# PX4FLOW2_0_CPU_X0.net
KiCad netlist of a schematic drawn in Altium Designer
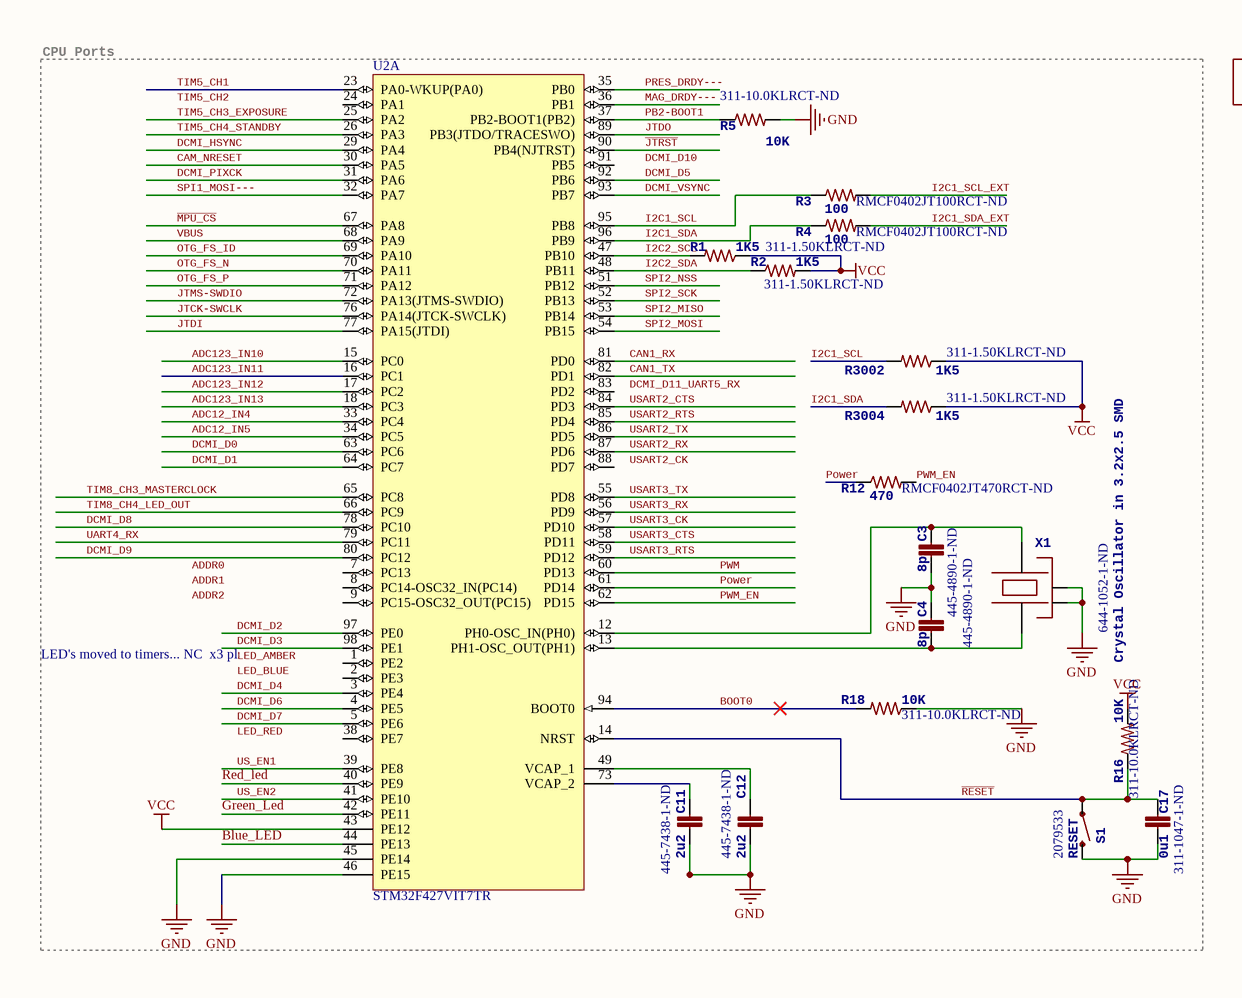
[diagram p0: PX4FLOW2.0_CPU_X0.SchDoc, left]
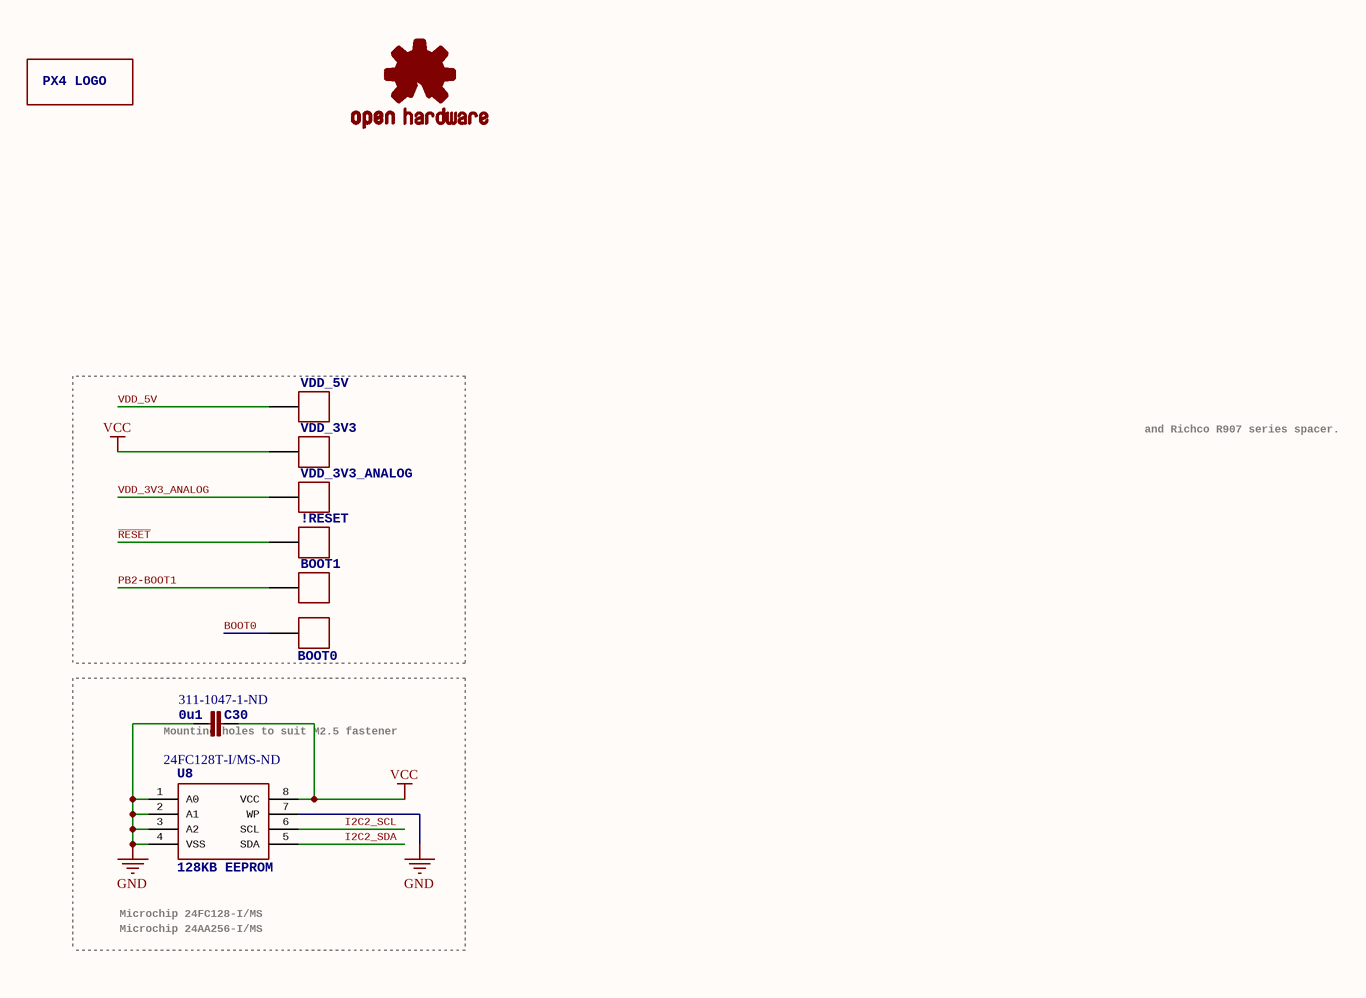
[diagram p1: PX4FLOW2.0_CPU_X0.SchDoc, right]

(export (version "E")
  (design (tool "Eeschema 10.0.6"))
  (components
    (comp (ref "!RESET") (value "PAD.04") (footprint "PAD.04X.04") (libsource (lib "") (part "PAD.04_1")))
    (comp (ref "BOOT0")
      (value "PAD.05")
      (footprint "PAD.05X.05")
      (libsource (lib "pixhawk2") (part "PAD.05"))
    )
    (comp (ref "BOOT1")
      (value "PAD.04")
      (footprint "PAD.04X.04")
      (libsource (lib "pixhawk2") (part "PAD.04"))
    )
    (comp (ref "C3")
      (value "8p")
      (footprint "0402-CAP")
      (description "CAP CER 8PF 50V C0G 0402")
      (fields
        (field (name "PARTNO") "C1005C0G1H080C")
        (field (name "SUPPLIER PART NUMBER 1") "445-4890-1-ND")
        (field (name "3DR_PARTNO") "ECM0710")
      )
      (libsource (lib "pixhawk2") (part "CAP0402"))
    )
    (comp (ref "C4")
      (value "8p")
      (footprint "0402-CAP")
      (description "CAP CER 8PF 50V C0G 0402")
      (fields
        (field (name "PARTNO") "C1005C0G1H080C")
        (field (name "SUPPLIER PART NUMBER 1") "445-4890-1-ND")
        (field (name "3DR_PARTNO") "ECM0710")
      )
      (libsource (lib "pixhawk2") (part "CAP0402"))
    )
    (comp (ref "C11")
      (value "2u2")
      (footprint "0603-CAP")
      (description "Capacitor, 2.2uF, 16V, 10%, X6S, 0603, Ceramic")
      (fields
        (field (name "PARTNO") "C1608X6S1C225K080AC")
        (field (name "SUPPLIER PART NUMBER 1") "445-7438-1-ND")
        (field (name "3DR_PARTNO") "ECM0619")
      )
      (libsource (lib "pixhawk2") (part "CAP0603"))
    )
    (comp (ref "C12")
      (value "2u2")
      (footprint "0603-CAP")
      (description "Capacitor, 2.2uF, 16V, 10%, X6S, 0603, Ceramic")
      (fields
        (field (name "PARTNO") "C1608X6S1C225K080AC")
        (field (name "SUPPLIER PART NUMBER 1") "445-7438-1-ND")
        (field (name "3DR_PARTNO") "ECM0619")
      )
      (libsource (lib "pixhawk2") (part "CAP0603"))
    )
    (comp (ref "C17")
      (value "0u1")
      (footprint "0402-CAP")
      (description "CapacitorStandard 0603 ceramic capacitor, and 0.1\" leaded capacitor.")
      (fields
        (field (name "PARTNO") "CC0402ZRY5V7BB104")
        (field (name "SUPPLIER PART NUMBER 1") "311-1047-1-ND")
      )
      (libsource (lib "pixhawk2") (part "CAP0402-CAP"))
    )
    (comp (ref "C30")
      (value "0u1")
      (footprint "0402-CAP")
      (description "CapacitorStandard 0603 ceramic capacitor, and 0.1\" leaded capacitor.")
      (fields
        (field (name "PARTNO") "CC0402ZRY5V7BB104")
        (field (name "SUPPLIER PART NUMBER 1") "311-1047-1-ND")
      )
      (libsource (lib "") (part "CAP0402-CAP_1"))
    )
    (comp (ref "R1")
      (value "1K5")
      (footprint "R0402")
      (description "RES 1.5K OHM 1/16W 1% 0402 SMD")
      (fields
        (field (name "PARTNO") "RC0402FR-071K5L")
        (field (name "SUPPLIER PART NUMBER 1") "311-1.50KLRCT-ND")
        (field (name "3DR_PARTNO") "ECM0803")
      )
      (libsource (lib "pixhawk2") (part "RESISTOR0402-RES"))
    )
    (comp (ref "R2")
      (value "1K5")
      (footprint "R0402")
      (description "RES 1.5K OHM 1/16W 1% 0402 SMD")
      (fields
        (field (name "PARTNO") "RC0402FR-071K5L")
        (field (name "SUPPLIER PART NUMBER 1") "311-1.50KLRCT-ND")
        (field (name "3DR_PARTNO") "ECM0803")
      )
      (libsource (lib "pixhawk2") (part "RESISTOR0402-RES"))
    )
    (comp (ref "R3")
      (value "100")
      (footprint "R0402")
      (fields
        (field (name "PARTNO") "RMCF0402JT100R")
        (field (name "SUPPLIER PART NUMBER 1") "RMCF0402JT100RCT-ND")
      )
      (libsource (lib "pixhawk2") (part "RESISTOR0402-RES"))
    )
    (comp (ref "R4")
      (value "100")
      (footprint "R0402")
      (fields
        (field (name "PARTNO") "RMCF0402JT100R")
        (field (name "SUPPLIER PART NUMBER 1") "RMCF0402JT100RCT-ND")
      )
      (libsource (lib "pixhawk2") (part "RESISTOR0402-RES"))
    )
    (comp (ref "R5")
      (value "10K")
      (footprint "R0402")
      (description "RES 10K OHM 1/16W 1% 0402 SMD")
      (fields
        (field (name "PARTNO") "RC0402FR-0710KL")
        (field (name "SUPPLIER PART NUMBER 1") "311-10.0KLRCT-ND")
        (field (name "3DR_PARTNO") "ECM0800")
      )
      (libsource (lib "pixhawk2") (part "RESISTOR0402-RES"))
    )
    (comp (ref "R12")
      (value "470")
      (footprint "R0402")
      (fields
        (field (name "PARTNO") "RMCF0402JT100R")
        (field (name "SUPPLIER PART NUMBER 1") "RMCF0402JT470RCT-ND")
      )
      (libsource (lib "pixhawk2") (part "RESISTOR0402-RES"))
    )
    (comp (ref "R16")
      (value "10K")
      (footprint "R0402")
      (description "RES 10K OHM 1/16W 1% 0402 SMD")
      (fields
        (field (name "PARTNO") "RC0402FR-0710KL")
        (field (name "SUPPLIER PART NUMBER 1") "311-10.0KLRCT-ND")
        (field (name "3DR_PARTNO") "ECM0800")
      )
      (libsource (lib "pixhawk2") (part "RESISTOR0402-RES"))
    )
    (comp (ref "R18")
      (value "10K")
      (footprint "R0402")
      (description "RES 10K OHM 1/16W 1% 0402 SMD")
      (fields
        (field (name "PARTNO") "RC0402FR-0710KL")
        (field (name "SUPPLIER PART NUMBER 1") "311-10.0KLRCT-ND")
        (field (name "3DR_PARTNO") "ECM0800")
      )
      (libsource (lib "pixhawk2") (part "RESISTOR0402-RES"))
    )
    (comp (ref "R3002")
      (value "1K5")
      (footprint "R0402")
      (description "RES 1.5K OHM 1/16W 1% 0402 SMD")
      (fields
        (field (name "PARTNO") "RC0402FR-071K5L")
        (field (name "SUPPLIER PART NUMBER 1") "311-1.50KLRCT-ND")
        (field (name "3DR_PARTNO") "ECM0803")
      )
      (libsource (lib "pixhawk2") (part "RESISTOR0402-RES"))
    )
    (comp (ref "R3004")
      (value "1K5")
      (footprint "R0402")
      (description "RES 1.5K OHM 1/16W 1% 0402 SMD")
      (fields
        (field (name "PARTNO") "RC0402FR-071K5L")
        (field (name "SUPPLIER PART NUMBER 1") "311-1.50KLRCT-ND")
        (field (name "3DR_PARTNO") "ECM0803")
      )
      (libsource (lib "3DR") (part "R0402"))
    )
    (comp (ref "S1")
      (value "RESET")
      (footprint "EVQP7J01K")
      (description "Switch")
      (fields (field (name "SUPPLIER PART NUMBER 1") "2079533"))
      (libsource (lib "pixhawk2") (part "SWITCH-MOMENTARY-2"))
    )
    (comp (ref "U$9")
      (value "PX4-LOGO-20MM")
      (footprint "PX4-LOGO-20MM")
      (fields (field (name "PX4LOGO") "PX4 LOGO"))
      (libsource (lib "pixhawk2") (part "PX4-LOGO-20MM"))
    )
    (comp (ref "U$10")
      (value "OSHW-LOGOS")
      (footprint "OSHW-LOGO-S")
      (libsource (lib "pixhawk2") (part "OSHW-LOGOS"))
    )
    (comp (ref "U2")
      (value "STM32F427VIT7TR")
      (footprint "STM-LQFP100_N")
      (fields (field (name "MANUFACTURER") "STMicroelectronics"))
      (libsource (lib "STMicroelectronics STM32 F4") (part "STM32F427VIT7TR"))
    )
    (comp (ref "U8")
      (value "128KB EEPROM")
      (footprint "MSOP-8")
      (fields
        (field (name "PARTNO") "24FC128-I/MS")
        (field (name "SUPPLIER PART NUMBER 1") "24FC128T-I/MS-ND")
      )
      (libsource (lib "pixhawk2") (part "EEPROM-I2CMSOP"))
    )
    (comp (ref "VDD_3V3")
      (value "PAD.04")
      (footprint "PAD.04X.04")
      (libsource (lib "pixhawk2") (part "PAD.04"))
    )
    (comp (ref "VDD_3V3_ANALOG")
      (value "PAD.04")
      (footprint "PAD.04X.04")
      (libsource (lib "pixhawk2") (part "PAD.04"))
    )
    (comp (ref "VDD_5V")
      (value "PAD.04")
      (footprint "PAD.04X.04")
      (libsource (lib "pixhawk2") (part "PAD.04"))
    )
    (comp (ref "X1")
      (value "Crystal Oscillator in 3.2x2.5 SMD")
      (footprint "OSCILLATOR-3.2X2.5")
      (description "CRYSTAL 24MHZ 8PF SMD")
      (fields
        (field (name "SUPPLIER PART NUMBER 1") "644-1052-1-ND")
        (field (name "3DR_PARTNO") "ECM0708")
        (field (name "PARTNO") "NX3225SA-24.000MHZ-STD-CSR-1")
      )
      (libsource (lib "pixhawk2") (part "OSCILLATOR-3.2X2.5"))
    )
  )
  (nets
    (net (code "1") (name "/ADC12_IN4") (class "Default")
      (node (ref "U2") (pin "33") (pinfunction "PC4_33") (pintype "bidirectional"))
    )
    (net (code "2") (name "/ADC12_IN5") (class "Default")
      (node (ref "U2") (pin "34") (pinfunction "PC5_34") (pintype "bidirectional"))
    )
    (net (code "3") (name "/ADC123_IN10") (class "Default")
      (node (ref "U2") (pin "15") (pinfunction "PC0_15") (pintype "bidirectional"))
    )
    (net (code "4") (name "/ADC123_IN11") (class "Default")
      (node (ref "U2") (pin "16") (pinfunction "PC1_16") (pintype "bidirectional"))
    )
    (net (code "5") (name "/ADC123_IN12") (class "Default")
      (node (ref "U2") (pin "17") (pinfunction "PC2_17") (pintype "bidirectional"))
    )
    (net (code "6") (name "/ADC123_IN13") (class "Default")
      (node (ref "U2") (pin "18") (pinfunction "PC3_18") (pintype "bidirectional"))
    )
    (net (code "10") (name "/BOOT0") (class "Default")
      (node (ref "BOOT0") (pin "P$1") (pinfunction "P$1_P$1") (pintype "passive"))
      (node (ref "R18") (pin "2") (pinfunction "2_2") (pintype "passive"))
      (node (ref "U2") (pin "94") (pinfunction "BOOT0_94") (pintype "input"))
    )
    (net (code "11") (name "/Blue_LED") (class "Default")
      (node (ref "U2") (pin "44") (pinfunction "PE13_44") (pintype "power_in"))
    )
    (net (code "12") (name "/CAM_NRESET") (class "Default")
      (node (ref "U2") (pin "30") (pinfunction "PA5_30") (pintype "bidirectional"))
    )
    (net (code "13") (name "/CAN1_RX") (class "Default")
      (node (ref "U2") (pin "81") (pinfunction "PD0_81") (pintype "bidirectional"))
    )
    (net (code "14") (name "/CAN1_TX") (class "Default")
      (node (ref "U2") (pin "82") (pinfunction "PD1_82") (pintype "bidirectional"))
    )
    (net (code "15") (name "/DCMI_D0") (class "Default")
      (node (ref "U2") (pin "63") (pinfunction "PC6_63") (pintype "bidirectional"))
    )
    (net (code "16") (name "/DCMI_D1") (class "Default")
      (node (ref "U2") (pin "64") (pinfunction "PC7_64") (pintype "bidirectional"))
    )
    (net (code "17") (name "/DCMI_D2") (class "Default")
      (node (ref "U2") (pin "97") (pinfunction "PE0_97") (pintype "bidirectional"))
    )
    (net (code "18") (name "/DCMI_D3") (class "Default")
      (node (ref "U2") (pin "98") (pinfunction "PE1_98") (pintype "bidirectional"))
    )
    (net (code "19") (name "/DCMI_D4") (class "Default")
      (node (ref "U2") (pin "3") (pinfunction "PE4_3") (pintype "bidirectional"))
    )
    (net (code "20") (name "/DCMI_D5") (class "Default")
      (node (ref "U2") (pin "92") (pinfunction "PB6_92") (pintype "bidirectional"))
    )
    (net (code "21") (name "/DCMI_D6") (class "Default")
      (node (ref "U2") (pin "4") (pinfunction "PE5_4") (pintype "bidirectional"))
    )
    (net (code "22") (name "/DCMI_D7") (class "Default")
      (node (ref "U2") (pin "5") (pinfunction "PE6_5") (pintype "bidirectional"))
    )
    (net (code "23") (name "/DCMI_D8") (class "Default")
      (node (ref "U2") (pin "78") (pinfunction "PC10_78") (pintype "bidirectional"))
    )
    (net (code "24") (name "/DCMI_D9") (class "Default")
      (node (ref "U2") (pin "80") (pinfunction "PC12_80") (pintype "bidirectional"))
    )
    (net (code "27") (name "/DCMI_HSYNC") (class "Default")
      (node (ref "U2") (pin "29") (pinfunction "PA4_29") (pintype "bidirectional"))
    )
    (net (code "28") (name "/DCMI_PIXCK") (class "Default")
      (node (ref "U2") (pin "31") (pinfunction "PA6_31") (pintype "bidirectional"))
    )
    (net (code "29") (name "/DCMI_VSYNC") (class "Default")
      (node (ref "U2") (pin "93") (pinfunction "PB7_93") (pintype "bidirectional"))
    )
    (net (code "30") (name "/Green_Led") (class "Default")
      (node (ref "U2") (pin "42") (pinfunction "PE11_42") (pintype "bidirectional"))
    )
    (net (code "31") (name "/I2C1_SCL") (class "Default")
      (node (ref "R3") (pin "1") (pinfunction "1_1") (pintype "passive"))
      (node (ref "R3002") (pin "2") (pinfunction "2_2") (pintype "passive"))
      (node (ref "U2") (pin "95") (pinfunction "PB8_95") (pintype "bidirectional"))
    )
    (net (code "32") (name "/I2C1_SCL_EXT") (class "Default")
      (node (ref "R3") (pin "2") (pinfunction "2_2") (pintype "passive"))
    )
    (net (code "33") (name "/I2C1_SDA") (class "Default")
      (node (ref "R3004") (pin "2") (pinfunction "2_2") (pintype "passive"))
      (node (ref "R4") (pin "1") (pinfunction "1_1") (pintype "passive"))
      (node (ref "U2") (pin "96") (pinfunction "PB9_96") (pintype "bidirectional"))
    )
    (net (code "34") (name "/I2C1_SDA_EXT") (class "Default")
      (node (ref "R4") (pin "2") (pinfunction "2_2") (pintype "passive"))
    )
    (net (code "35") (name "/I2C2_SCL") (class "Default")
      (node (ref "R1") (pin "2") (pinfunction "2_2") (pintype "passive"))
      (node (ref "U2") (pin "47") (pinfunction "PB10_47") (pintype "bidirectional"))
      (node (ref "U8") (pin "6") (pinfunction "SCL_6") (pintype "passive"))
    )
    (net (code "36") (name "/I2C2_SDA") (class "Default")
      (node (ref "R2") (pin "1") (pinfunction "1_1") (pintype "passive"))
      (node (ref "U2") (pin "48") (pinfunction "PB11_48") (pintype "bidirectional"))
      (node (ref "U8") (pin "5") (pinfunction "SDA_5") (pintype "passive"))
    )
    (net (code "37") (name "/JTCK-SWCLK") (class "Default")
      (node (ref "U2") (pin "76") (pinfunction "PA14(JTCK-SWCLK)_76") (pintype "bidirectional"))
    )
    (net (code "38") (name "/JTDI") (class "Default")
      (node (ref "U2") (pin "77") (pinfunction "PA15(JTDI)_77") (pintype "bidirectional"))
    )
    (net (code "39") (name "/JTDO") (class "Default")
      (node (ref "U2") (pin "89") (pinfunction "PB3(JTDO/TRACESWO)_89") (pintype "bidirectional"))
    )
    (net (code "40") (name "/JTMS-SWDIO") (class "Default")
      (node (ref "U2") (pin "72") (pinfunction "PA13(JTMS-SWDIO)_72") (pintype "bidirectional"))
    )
    (net (code "44") (name "/MAG_DRDY---") (class "Default")
      (node (ref "U2") (pin "36") (pinfunction "PB1_36") (pintype "bidirectional"))
    )
    (net (code "45") (name "/OTG_FS_ID") (class "Default")
      (node (ref "U2") (pin "69") (pinfunction "PA10_69") (pintype "bidirectional"))
    )
    (net (code "46") (name "/OTG_FS_N") (class "Default")
      (node (ref "U2") (pin "70") (pinfunction "PA11_70") (pintype "bidirectional"))
    )
    (net (code "47") (name "/OTG_FS_P") (class "Default")
      (node (ref "U2") (pin "71") (pinfunction "PA12_71") (pintype "bidirectional"))
    )
    (net (code "48") (name "/PB2-BOOT1") (class "Default")
      (node (ref "BOOT1") (pin "P$1") (pinfunction "P$1_P$1") (pintype "passive"))
      (node (ref "R5") (pin "1") (pinfunction "1_1") (pintype "passive"))
      (node (ref "U2") (pin "37") (pinfunction "PB2-BOOT1(PB2)_37") (pintype "bidirectional"))
    )
    (net (code "49") (name "/PRES_DRDY---") (class "Default")
      (node (ref "U2") (pin "35") (pinfunction "PB0_35") (pintype "bidirectional"))
    )
    (net (code "50") (name "/PWM") (class "Default")
      (node (ref "U2") (pin "60") (pinfunction "PD13_60") (pintype "bidirectional"))
    )
    (net (code "51") (name "/PWM_EN") (class "Default")
      (node (ref "R12") (pin "2") (pinfunction "2_2") (pintype "passive"))
      (node (ref "U2") (pin "62") (pinfunction "PD15_62") (pintype "bidirectional"))
    )
    (net (code "52") (name "/Power") (class "Default")
      (node (ref "R12") (pin "1") (pinfunction "1_1") (pintype "passive"))
      (node (ref "U2") (pin "61") (pinfunction "PD14_61") (pintype "bidirectional"))
    )
    (net (code "53") (name "/Red_led") (class "Default")
      (node (ref "U2") (pin "40") (pinfunction "PE9_40") (pintype "bidirectional"))
    )
    (net (code "54") (name "/SPI1_MOSI---") (class "Default")
      (node (ref "U2") (pin "32") (pinfunction "PA7_32") (pintype "bidirectional"))
    )
    (net (code "55") (name "/SPI2_MISO") (class "Default")
      (node (ref "U2") (pin "53") (pinfunction "PB14_53") (pintype "bidirectional"))
    )
    (net (code "56") (name "/SPI2_MOSI") (class "Default")
      (node (ref "U2") (pin "54") (pinfunction "PB15_54") (pintype "bidirectional"))
    )
    (net (code "57") (name "/SPI2_NSS") (class "Default")
      (node (ref "U2") (pin "51") (pinfunction "PB12_51") (pintype "bidirectional"))
    )
    (net (code "58") (name "/SPI2_SCK") (class "Default")
      (node (ref "U2") (pin "52") (pinfunction "PB13_52") (pintype "bidirectional"))
    )
    (net (code "59") (name "/TIM5_CH1") (class "Default")
      (node (ref "U2") (pin "23") (pinfunction "PA0-WKUP(PA0)_23") (pintype "bidirectional"))
    )
    (net (code "61") (name "/TIM5_CH3_EXPOSURE") (class "Default")
      (node (ref "U2") (pin "25") (pinfunction "PA2_25") (pintype "bidirectional"))
    )
    (net (code "62") (name "/TIM5_CH4_STANDBY") (class "Default")
      (node (ref "U2") (pin "26") (pinfunction "PA3_26") (pintype "bidirectional"))
    )
    (net (code "63") (name "/TIM8_CH3_MASTERCLOCK") (class "Default")
      (node (ref "U2") (pin "65") (pinfunction "PC8_65") (pintype "bidirectional"))
    )
    (net (code "64") (name "/TIM8_CH4_LED_OUT") (class "Default")
      (node (ref "U2") (pin "66") (pinfunction "PC9_66") (pintype "bidirectional"))
    )
    (net (code "65") (name "/UART4_RX") (class "Default")
      (node (ref "U2") (pin "79") (pinfunction "PC11_79") (pintype "bidirectional"))
    )
    (net (code "67") (name "/USART2_CTS") (class "Default")
      (node (ref "U2") (pin "84") (pinfunction "PD3_84") (pintype "bidirectional"))
    )
    (net (code "68") (name "/USART2_RTS") (class "Default")
      (node (ref "U2") (pin "85") (pinfunction "PD4_85") (pintype "bidirectional"))
    )
    (net (code "69") (name "/USART2_RX") (class "Default")
      (node (ref "U2") (pin "87") (pinfunction "PD6_87") (pintype "bidirectional"))
    )
    (net (code "70") (name "/USART2_TX") (class "Default")
      (node (ref "U2") (pin "86") (pinfunction "PD5_86") (pintype "bidirectional"))
    )
    (net (code "71") (name "/USART3_CK") (class "Default")
      (node (ref "U2") (pin "57") (pinfunction "PD10_57") (pintype "bidirectional"))
    )
    (net (code "72") (name "/USART3_CTS") (class "Default")
      (node (ref "U2") (pin "58") (pinfunction "PD11_58") (pintype "bidirectional"))
    )
    (net (code "73") (name "/USART3_RTS") (class "Default")
      (node (ref "U2") (pin "59") (pinfunction "PD12_59") (pintype "bidirectional"))
    )
    (net (code "74") (name "/USART3_RX") (class "Default")
      (node (ref "U2") (pin "56") (pinfunction "PD9_56") (pintype "bidirectional"))
    )
    (net (code "75") (name "/USART3_TX") (class "Default")
      (node (ref "U2") (pin "55") (pinfunction "PD8_55") (pintype "bidirectional"))
    )
    (net (code "76") (name "/US_EN1") (class "Default")
      (node (ref "U2") (pin "39") (pinfunction "PE8_39") (pintype "bidirectional"))
    )
    (net (code "77") (name "/US_EN2") (class "Default")
      (node (ref "U2") (pin "41") (pinfunction "PE10_41") (pintype "bidirectional"))
    )
    (net (code "78") (name "/VBUS") (class "Default")
      (node (ref "U2") (pin "68") (pinfunction "PA9_68") (pintype "bidirectional"))
    )
    (net (code "79") (name "/VDD_3V3_ANALOG") (class "Default")
      (node (ref "VDD_3V3_ANALOG") (pin "P$1") (pinfunction "P$1_P$1") (pintype "passive"))
    )
    (net (code "80") (name "/VDD_5V") (class "Default")
      (node (ref "VDD_5V") (pin "P$1") (pinfunction "P$1_P$1") (pintype "passive"))
    )
    (net (code "81") (name "/~{JTRST}") (class "Default")
      (node (ref "U2") (pin "90") (pinfunction "PB4(NJTRST)_90") (pintype "bidirectional"))
    )
    (net (code "82") (name "/~{MPU_CS}") (class "Default")
      (node (ref "U2") (pin "67") (pinfunction "PA8_67") (pintype "bidirectional"))
    )
    (net (code "83") (name "/~{RESET}") (class "Default")
      (node (ref "!RESET") (pin "P1") (pinfunction "P1_P1") (pintype "passive"))
      (node (ref "C17") (pin "2") (pinfunction "2_2") (pintype "passive"))
      (node (ref "R16") (pin "1") (pinfunction "1_1") (pintype "passive"))
      (node (ref "S1") (pin "A1") (pinfunction "1_A1") (pintype "passive"))
      (node (ref "U2") (pin "14") (pinfunction "NRST_14") (pintype "bidirectional"))
    )
    (net (code "84") (name "GND") (class "Default")
      (node (ref "C11") (pin "P$2") (pinfunction "2_P$2") (pintype "passive"))
      (node (ref "C12") (pin "P$2") (pinfunction "2_P$2") (pintype "passive"))
      (node (ref "C17") (pin "1") (pinfunction "1_1") (pintype "passive"))
      (node (ref "C3") (pin "P$2") (pinfunction "2_P$2") (pintype "passive"))
      (node (ref "C30") (pin "2") (pinfunction "2_2") (pintype "passive"))
      (node (ref "C4") (pin "P$1") (pinfunction "1_P$1") (pintype "passive"))
      (node (ref "R18") (pin "1") (pinfunction "1_1") (pintype "passive"))
      (node (ref "R5") (pin "2") (pinfunction "2_2") (pintype "passive"))
      (node (ref "S1") (pin "B3") (pinfunction "2_B3") (pintype "passive"))
      (node (ref "U2") (pin "45") (pinfunction "PE14_45") (pintype "power_in"))
      (node (ref "U2") (pin "46") (pinfunction "PE15_46") (pintype "power_in"))
      (node (ref "U8") (pin "1") (pinfunction "A0_1") (pintype "power_in"))
      (node (ref "U8") (pin "2") (pinfunction "A1_2") (pintype "power_in"))
      (node (ref "U8") (pin "3") (pinfunction "A2_3") (pintype "power_in"))
      (node (ref "U8") (pin "4") (pinfunction "VSS_4") (pintype "power_in"))
      (node (ref "U8") (pin "7") (pinfunction "WP_7") (pintype "power_in"))
      (node (ref "X1") (pin "2") (pinfunction "NC_2_2") (pintype "power_in"))
      (node (ref "X1") (pin "4") (pinfunction "NC_4_4") (pintype "power_in"))
    )
    (net (code "85") (name "Net-(C3-1)") (class "Default")
      (node (ref "C3") (pin "P$1") (pinfunction "1_P$1") (pintype "passive"))
      (node (ref "U2") (pin "12") (pinfunction "PH0-OSC_IN(PH0)_12") (pintype "bidirectional"))
      (node (ref "X1") (pin "3") (pinfunction "3_3") (pintype "passive"))
    )
    (net (code "86") (name "Net-(C4-2)") (class "Default")
      (node (ref "C4") (pin "P$2") (pinfunction "2_P$2") (pintype "passive"))
      (node (ref "U2") (pin "13") (pinfunction "PH1-OSC_OUT(PH1)_13") (pintype "bidirectional"))
      (node (ref "X1") (pin "1") (pinfunction "1_1") (pintype "passive"))
    )
    (net (code "87") (name "Net-(C11-1)") (class "Default")
      (node (ref "C11") (pin "P$1") (pinfunction "1_P$1") (pintype "passive"))
      (node (ref "U2") (pin "73") (pinfunction "VCAP_2_73") (pintype "power_in"))
    )
    (net (code "88") (name "Net-(C12-1)") (class "Default")
      (node (ref "C12") (pin "P$1") (pinfunction "1_P$1") (pintype "passive"))
      (node (ref "U2") (pin "49") (pinfunction "VCAP_1_49") (pintype "power_in"))
    )
    (net (code "89") (name "VCC") (class "Default")
      (node (ref "C30") (pin "1") (pinfunction "1_1") (pintype "passive"))
      (node (ref "R1") (pin "1") (pinfunction "1_1") (pintype "passive"))
      (node (ref "R16") (pin "2") (pinfunction "2_2") (pintype "passive"))
      (node (ref "R2") (pin "2") (pinfunction "2_2") (pintype "passive"))
      (node (ref "R3002") (pin "1") (pinfunction "1_1") (pintype "passive"))
      (node (ref "R3004") (pin "1") (pinfunction "1_1") (pintype "passive"))
      (node (ref "U2") (pin "43") (pinfunction "PE12_43") (pintype "power_in"))
      (node (ref "U8") (pin "8") (pinfunction "VCC_8") (pintype "power_in"))
      (node (ref "VDD_3V3") (pin "P$1") (pinfunction "P$1_P$1") (pintype "passive"))
    )
    (net (code "90") (name "unconnected-(U2A-PA1-Pad24)") (class "Default")
      (node (ref "U2") (pin "24") (pinfunction "PA1_24") (pintype "bidirectional"))
    )
    (net (code "91") (name "unconnected-(U2A-PB5-Pad91)") (class "Default")
      (node (ref "U2") (pin "91") (pinfunction "PB5_91") (pintype "bidirectional"))
    )
    (net (code "92") (name "unconnected-(U2A-PC13-Pad7)") (class "Default")
      (node (ref "U2") (pin "7") (pinfunction "PC13_7") (pintype "bidirectional"))
    )
    (net (code "93") (name "unconnected-(U2A-PC14-OSC32_IN(PC14)-Pad8)") (class "Default")
      (node (ref "U2") (pin "8") (pinfunction "PC14-OSC32_IN(PC14)_8") (pintype "bidirectional"))
    )
    (net (code "94") (name "unconnected-(U2A-PC15-OSC32_OUT(PC15)-Pad9)") (class "Default")
      (node (ref "U2") (pin "9") (pinfunction "PC15-OSC32_OUT(PC15)_9") (pintype "bidirectional"))
    )
    (net (code "95") (name "unconnected-(U2A-PD2-Pad83)") (class "Default")
      (node (ref "U2") (pin "83") (pinfunction "PD2_83") (pintype "bidirectional"))
    )
    (net (code "96") (name "unconnected-(U2A-PD7-Pad88)") (class "Default")
      (node (ref "U2") (pin "88") (pinfunction "PD7_88") (pintype "bidirectional"))
    )
    (net (code "97") (name "unconnected-(U2A-PE2-Pad1)") (class "Default")
      (node (ref "U2") (pin "1") (pinfunction "PE2_1") (pintype "bidirectional"))
    )
    (net (code "98") (name "unconnected-(U2A-PE3-Pad2)") (class "Default")
      (node (ref "U2") (pin "2") (pinfunction "PE3_2") (pintype "bidirectional"))
    )
    (net (code "99") (name "unconnected-(U2A-PE7-Pad38)") (class "Default")
      (node (ref "U2") (pin "38") (pinfunction "PE7_38") (pintype "bidirectional"))
    )
  )
)
